# 02_-_CONNECTORS.net
KiCad netlist of a schematic drawn in Altium Designer
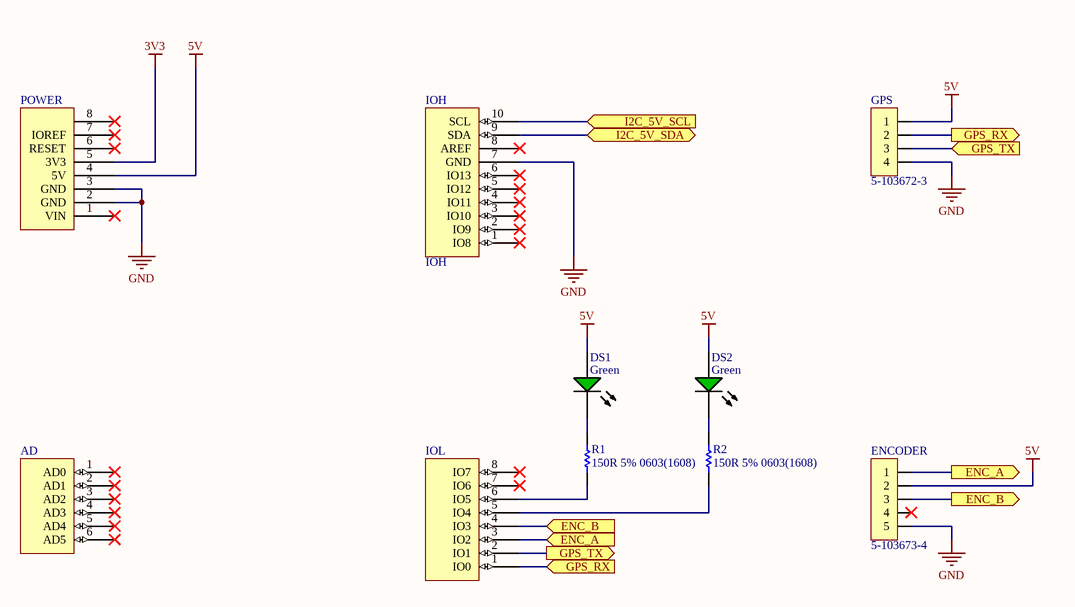
[diagram p0: [02] - CONNECTORS.SchDoc]

(export (version "E")
  (design (tool "Eeschema 10.0.6"))
  (components
    (comp (ref "AD")
      (value "AD")
      (footprint "Header:Header 6x1 8.5mm")
      (libsource (lib "Header") (part "AD"))
    )
    (comp (ref "DS1")
      (value "APG1608CGKC/T")
      (footprint "KING-LED0603-25-GREEN_V")
      (description "LED, SMT, 0603(1608), 0.25mm Thickness, Green")
      (fields
        (field (name "COLOR") "Green")
        (field (name "MANUFACTURER PART NUMBER") "APT1608MGC")
        (field (name "DIGI-KEY PART NUMBER") "754-1118-1-ND")
      )
      (libsource (lib "Altium Content Vault") (part "CMP-0239-00001-1"))
    )
    (comp (ref "DS2")
      (value "APG1608CGKC/T")
      (footprint "KING-LED0603-25-GREEN_V")
      (description "LED, SMT, 0603(1608), 0.25mm Thickness, Green")
      (fields
        (field (name "COLOR") "Green")
        (field (name "MANUFACTURER PART NUMBER") "APT1608MGC")
        (field (name "DIGI-KEY PART NUMBER") "754-1118-1-ND")
      )
      (libsource (lib "Altium Content Vault") (part "CMP-0239-00001-1"))
    )
    (comp (ref "ENCODER")
      (value "5-103673-4")
      (footprint "Header_5-103673-4_TE")
      (libsource (lib "Header_5-103673-4_TE") (part "Header_5-103673-4_TE"))
    )
    (comp (ref "GPS")
      (value "5-103672-3")
      (footprint "PCBComponent_1")
      (libsource (lib "Header_5-103672-3_TE") (part "Header_5-103672-3_TE"))
    )
    (comp (ref "IOH")
      (value "IOH")
      (footprint "Header:Header 10x1 8.5mm")
      (libsource (lib "Header") (part "IOH"))
    )
    (comp (ref "IOL") (value "IOL") (footprint "Header 8x1 8.5mm") (libsource (lib "Header") (part "IOL")))
    (comp (ref "POWER")
      (value "POWER_UNO")
      (footprint "Header 8x1 8.5mm")
      (libsource (lib "Header") (part "POWER_UNO"))
    )
    (comp (ref "R1")
      (value "150R 5% 0603(1608)")
      (footprint "RESC0603(1608)_L")
      (description "150R 0.1W 5% 0603 (1608 Metric)  SMD")
      (fields (field (name "TOLERANCE") "5 %") (field (name "POWER") "0.1 W"))
      (libsource (lib "Altium Content Vault") (part "CMP-1012-00054-1"))
    )
    (comp (ref "R2")
      (value "150R 5% 0603(1608)")
      (footprint "RESC0603(1608)_L")
      (description "150R 0.1W 5% 0603 (1608 Metric)  SMD")
      (fields (field (name "TOLERANCE") "5 %") (field (name "POWER") "0.1 W"))
      (libsource (lib "Altium Content Vault") (part "CMP-1012-00054-1"))
    )
  )
  (nets
    (net (code "1") (name "/ENC_A") (class "Default")
      (node (ref "ENCODER") (pin "1") (pinfunction "1_1") (pintype "passive"))
      (node (ref "IOL") (pin "3") (pinfunction "IO2_3") (pintype "bidirectional"))
    )
    (net (code "2") (name "/ENC_B") (class "Default")
      (node (ref "ENCODER") (pin "3") (pinfunction "3_3") (pintype "passive"))
      (node (ref "IOL") (pin "4") (pinfunction "IO3_4") (pintype "bidirectional"))
    )
    (net (code "3") (name "/GPS_RX") (class "Default")
      (node (ref "GPS") (pin "2") (pinfunction "2_2") (pintype "passive"))
      (node (ref "IOL") (pin "1") (pinfunction "IO0_1") (pintype "bidirectional"))
    )
    (net (code "4") (name "/GPS_TX") (class "Default")
      (node (ref "GPS") (pin "3") (pinfunction "3_3") (pintype "passive"))
      (node (ref "IOL") (pin "2") (pinfunction "IO1_2") (pintype "bidirectional"))
    )
    (net (code "5") (name "/I2C_5V_SCL") (class "Default")
      (node (ref "IOH") (pin "10") (pinfunction "SCL_10") (pintype "bidirectional"))
    )
    (net (code "6") (name "/I2C_5V_SDA") (class "Default")
      (node (ref "IOH") (pin "9") (pinfunction "SDA_9") (pintype "bidirectional"))
    )
    (net (code "7") (name "3V3") (class "Default")
      (node (ref "POWER") (pin "5") (pinfunction "3V3_5") (pintype "power_in"))
    )
    (net (code "8") (name "5V") (class "Default")
      (node (ref "DS1") (pin "1") (pinfunction "A_1") (pintype "passive"))
      (node (ref "DS2") (pin "1") (pinfunction "A_1") (pintype "passive"))
      (node (ref "ENCODER") (pin "2") (pinfunction "2_2") (pintype "passive"))
      (node (ref "GPS") (pin "1") (pinfunction "1_1") (pintype "passive"))
      (node (ref "POWER") (pin "4") (pinfunction "5V_4") (pintype "power_in"))
    )
    (net (code "9") (name "GND") (class "Default")
      (node (ref "ENCODER") (pin "5") (pinfunction "5_5") (pintype "passive"))
      (node (ref "GPS") (pin "4") (pinfunction "4_4") (pintype "passive"))
      (node (ref "IOH") (pin "7") (pinfunction "GND_7") (pintype "power_in"))
      (node (ref "POWER") (pin "2") (pinfunction "GND_2") (pintype "power_in"))
      (node (ref "POWER") (pin "3") (pinfunction "GND_3") (pintype "power_in"))
    )
    (net (code "10") (name "Net-(DS1-K)") (class "Default")
      (node (ref "DS1") (pin "2") (pinfunction "K_2") (pintype "passive"))
      (node (ref "R1") (pin "1") (pinfunction "1_1") (pintype "passive"))
    )
    (net (code "11") (name "Net-(DS2-K)") (class "Default")
      (node (ref "DS2") (pin "2") (pinfunction "K_2") (pintype "passive"))
      (node (ref "R2") (pin "1") (pinfunction "1_1") (pintype "passive"))
    )
    (net (code "12") (name "Net-(IOL-IO4)") (class "Default")
      (node (ref "IOL") (pin "5") (pinfunction "IO4_5") (pintype "bidirectional"))
      (node (ref "R2") (pin "2") (pinfunction "2_2") (pintype "passive"))
    )
    (net (code "13") (name "Net-(IOL-IO5)") (class "Default")
      (node (ref "IOL") (pin "6") (pinfunction "IO5_6") (pintype "bidirectional"))
      (node (ref "R1") (pin "2") (pinfunction "2_2") (pintype "passive"))
    )
    (net (code "14") (name "unconnected-(AD-AD0-Pad1)") (class "Default")
      (node (ref "AD") (pin "1") (pinfunction "AD0_1") (pintype "bidirectional+no_connect"))
    )
    (net (code "15") (name "unconnected-(AD-AD1-Pad2)") (class "Default")
      (node (ref "AD") (pin "2") (pinfunction "AD1_2") (pintype "bidirectional+no_connect"))
    )
    (net (code "16") (name "unconnected-(AD-AD2-Pad3)") (class "Default")
      (node (ref "AD") (pin "3") (pinfunction "AD2_3") (pintype "bidirectional+no_connect"))
    )
    (net (code "17") (name "unconnected-(AD-AD3-Pad4)") (class "Default")
      (node (ref "AD") (pin "4") (pinfunction "AD3_4") (pintype "bidirectional+no_connect"))
    )
    (net (code "18") (name "unconnected-(AD-AD4-Pad5)") (class "Default")
      (node (ref "AD") (pin "5") (pinfunction "AD4_5") (pintype "bidirectional+no_connect"))
    )
    (net (code "19") (name "unconnected-(AD-AD5-Pad6)") (class "Default")
      (node (ref "AD") (pin "6") (pinfunction "AD5_6") (pintype "bidirectional+no_connect"))
    )
    (net (code "20") (name "unconnected-(ENCODER-Pad4)") (class "Default")
      (node (ref "ENCODER") (pin "4") (pinfunction "4_4") (pintype "passive+no_connect"))
    )
    (net (code "21") (name "unconnected-(IOH-AREF-Pad8)") (class "Default")
      (node (ref "IOH") (pin "8") (pinfunction "AREF_8") (pintype "passive+no_connect"))
    )
    (net (code "22") (name "unconnected-(IOH-IO8-Pad1)") (class "Default")
      (node (ref "IOH") (pin "1") (pinfunction "IO8_1") (pintype "bidirectional+no_connect"))
    )
    (net (code "23") (name "unconnected-(IOH-IO9-Pad2)") (class "Default")
      (node (ref "IOH") (pin "2") (pinfunction "IO9_2") (pintype "bidirectional+no_connect"))
    )
    (net (code "24") (name "unconnected-(IOH-IO10-Pad3)") (class "Default")
      (node (ref "IOH") (pin "3") (pinfunction "IO10_3") (pintype "bidirectional+no_connect"))
    )
    (net (code "25") (name "unconnected-(IOH-IO11-Pad4)") (class "Default")
      (node (ref "IOH") (pin "4") (pinfunction "IO11_4") (pintype "bidirectional+no_connect"))
    )
    (net (code "26") (name "unconnected-(IOH-IO12-Pad5)") (class "Default")
      (node (ref "IOH") (pin "5") (pinfunction "IO12_5") (pintype "bidirectional+no_connect"))
    )
    (net (code "27") (name "unconnected-(IOH-IO13-Pad6)") (class "Default")
      (node (ref "IOH") (pin "6") (pinfunction "IO13_6") (pintype "bidirectional+no_connect"))
    )
    (net (code "28") (name "unconnected-(IOL-IO6-Pad7)") (class "Default")
      (node (ref "IOL") (pin "7") (pinfunction "IO6_7") (pintype "bidirectional+no_connect"))
    )
    (net (code "29") (name "unconnected-(IOL-IO7-Pad8)") (class "Default")
      (node (ref "IOL") (pin "8") (pinfunction "IO7_8") (pintype "bidirectional+no_connect"))
    )
    (net (code "30") (name "unconnected-(POWER-IOREF-Pad7)") (class "Default")
      (node (ref "POWER") (pin "7") (pinfunction "IOREF_7") (pintype "power_in+no_connect"))
    )
    (net (code "31") (name "unconnected-(POWER-Pad8)") (class "Default")
      (node (ref "POWER") (pin "8") (pintype "passive+no_connect"))
    )
    (net (code "32") (name "unconnected-(POWER-RESET-Pad6)") (class "Default")
      (node (ref "POWER") (pin "6") (pinfunction "RESET_6") (pintype "passive+no_connect"))
    )
    (net (code "33") (name "unconnected-(POWER-VIN-Pad1)") (class "Default")
      (node (ref "POWER") (pin "1") (pinfunction "VIN_1") (pintype "power_in+no_connect"))
    )
  )
)
